# 03_Pressure_and_Flow.net
KiCad netlist of a schematic drawn in Altium Designer
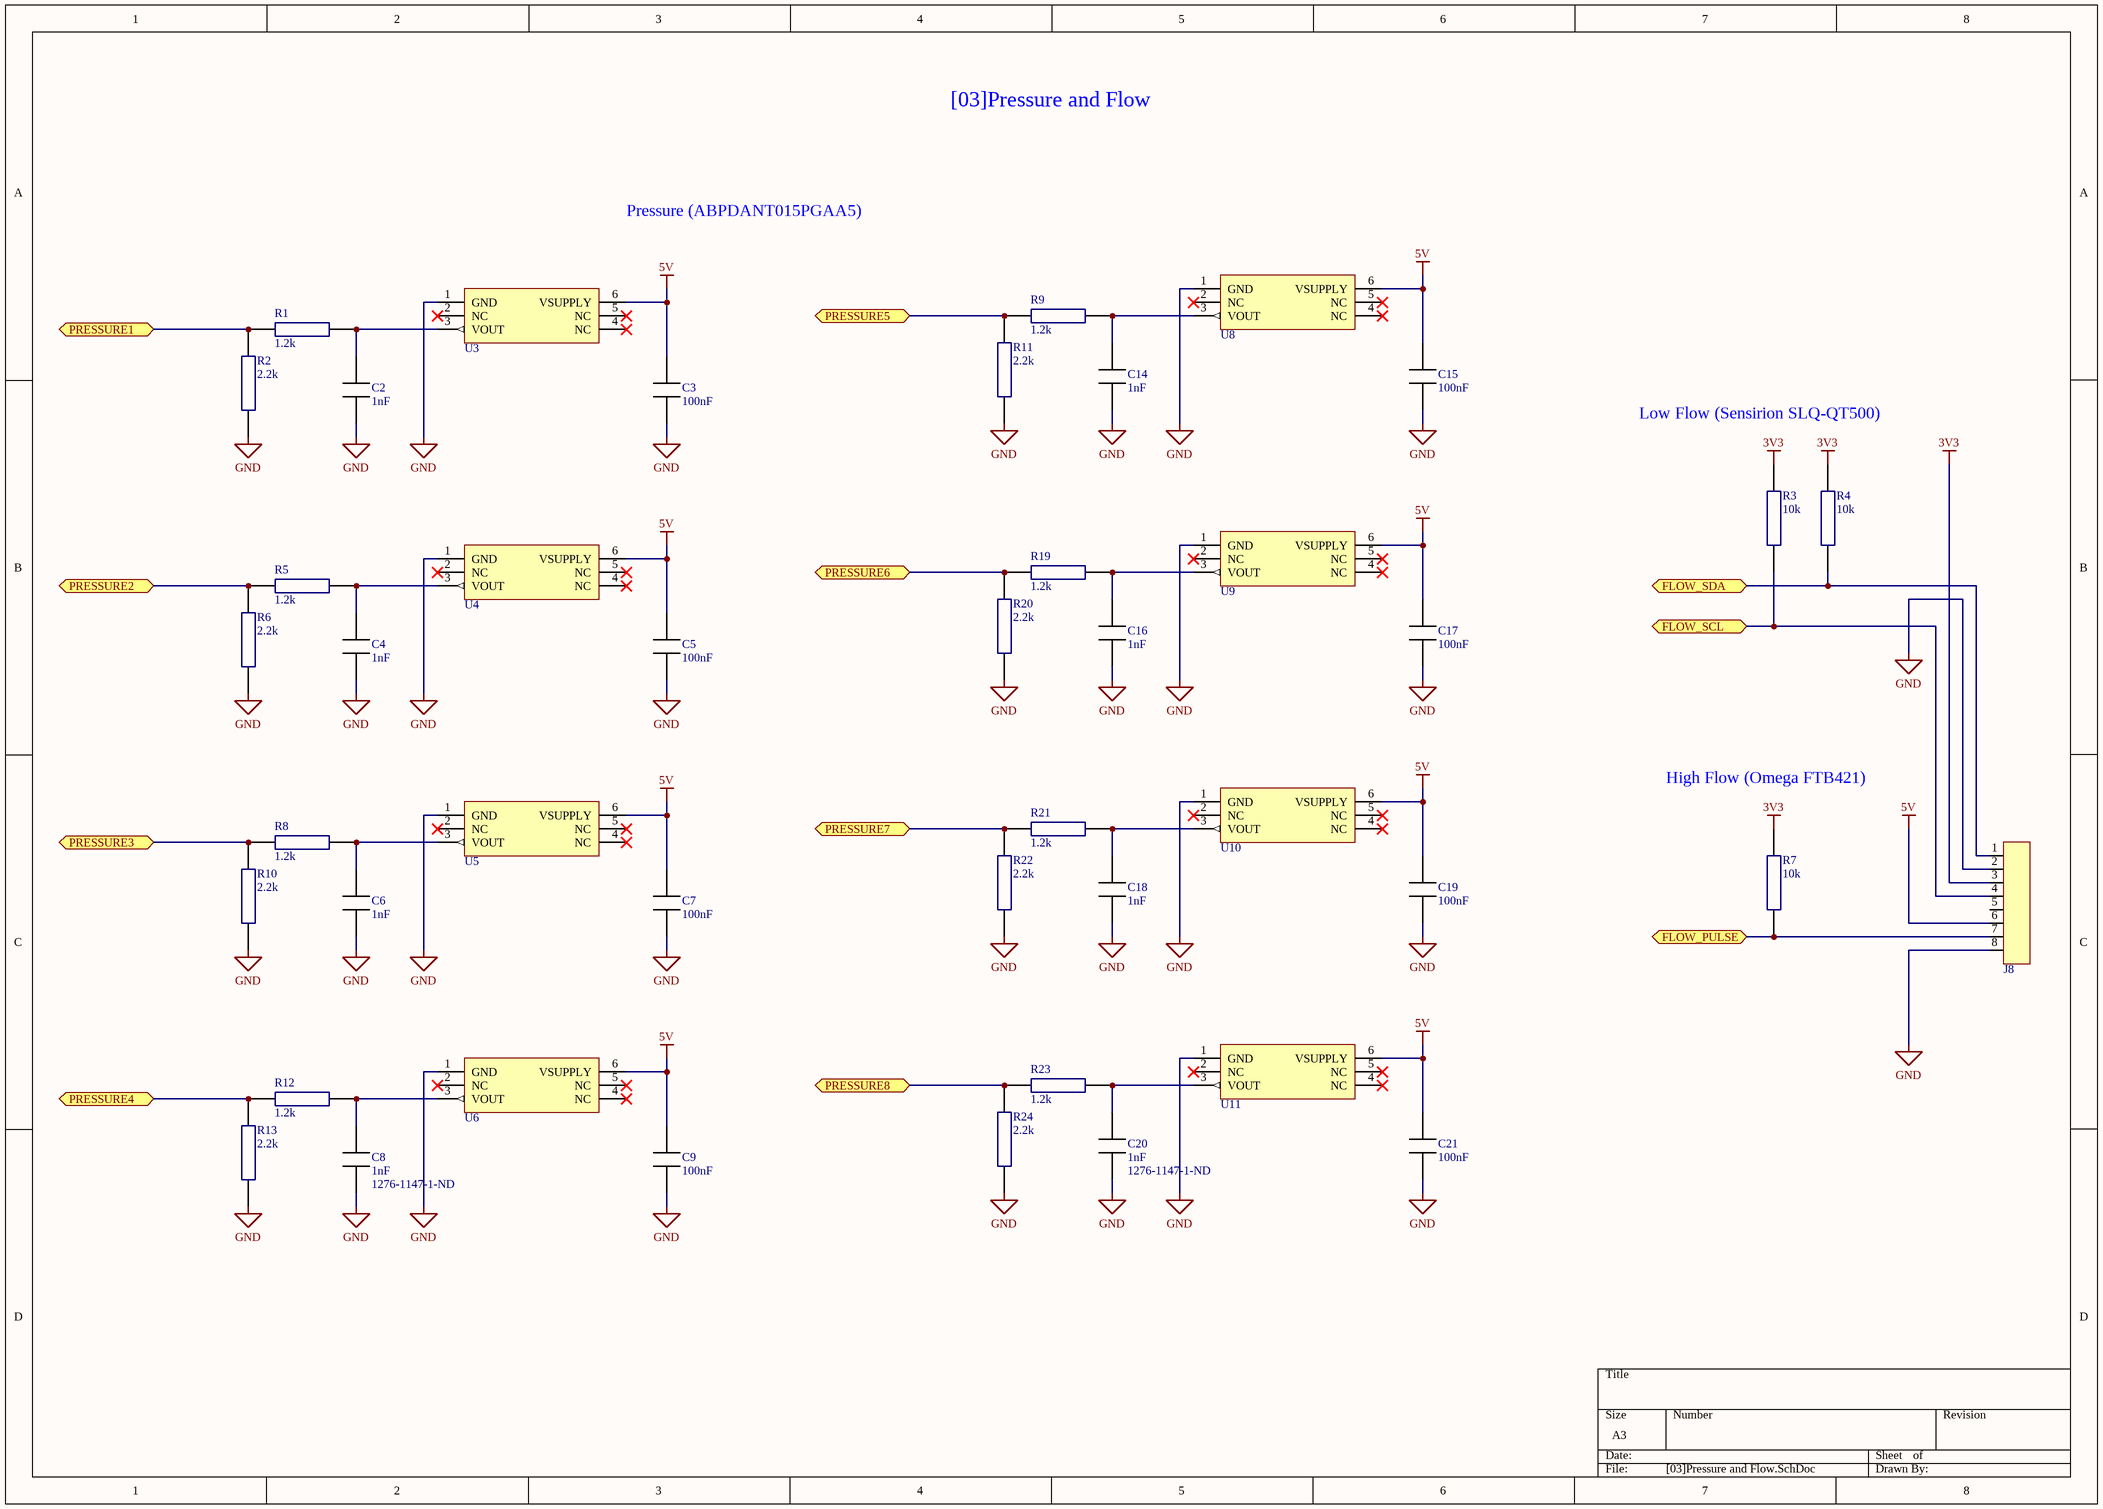
[diagram p0: [03]Pressure and Flow.SchDoc]

(export (version "E")
  (design (tool "Eeschema 10.0.6"))
  (components
    (comp (ref "C2")
      (value "1nF")
      (footprint "CAPC2012X09N")
      (description "CAP CER 1nF 50V C0G/NP0 0805")
      (fields
        (field (name "MANUFACTURER") "Samsung Electro-Mechanics America, Inc.")
        (field (name "MANUFACTURER PART NUMBER") "CL21F104ZBCNNNC")
      )
      (libsource (lib "AMMDK Parts") (part "CL21C102JBCNNNC"))
    )
    (comp (ref "C3")
      (value "100nF")
      (footprint "CAPC2012X09N")
      (description "CAP CER 0.1UF 50V Y5V 0805")
      (fields
        (field (name "MANUFACTURER") "Samsung Electro-Mechanics America, Inc.")
        (field (name "MANUFACTURER PART NUMBER") "CL21F104ZBCNNNC")
      )
      (libsource (lib "AMMDK Parts") (part "CL21F104ZBCNNNC"))
    )
    (comp (ref "C4")
      (value "1nF")
      (footprint "CAPC2012X09N")
      (description "CAP CER 1nF 50V C0G/NP0 0805")
      (fields
        (field (name "MANUFACTURER") "Samsung Electro-Mechanics America, Inc.")
        (field (name "MANUFACTURER PART NUMBER") "CL21F104ZBCNNNC")
      )
      (libsource (lib "AMMDK Parts") (part "CL21C102JBCNNNC"))
    )
    (comp (ref "C5")
      (value "100nF")
      (footprint "CAPC2012X09N")
      (description "CAP CER 0.1UF 50V Y5V 0805")
      (fields
        (field (name "MANUFACTURER") "Samsung Electro-Mechanics America, Inc.")
        (field (name "MANUFACTURER PART NUMBER") "CL21F104ZBCNNNC")
      )
      (libsource (lib "AMMDK Parts") (part "CL21F104ZBCNNNC"))
    )
    (comp (ref "C6")
      (value "1nF")
      (footprint "CAPC2012X09N")
      (description "CAP CER 1nF 50V C0G/NP0 0805")
      (fields
        (field (name "MANUFACTURER") "Samsung Electro-Mechanics America, Inc.")
        (field (name "MANUFACTURER PART NUMBER") "CL21F104ZBCNNNC")
      )
      (libsource (lib "AMMDK Parts") (part "CL21C102JBCNNNC"))
    )
    (comp (ref "C7")
      (value "100nF")
      (footprint "CAPC2012X09N")
      (description "CAP CER 0.1UF 50V Y5V 0805")
      (fields
        (field (name "MANUFACTURER") "Samsung Electro-Mechanics America, Inc.")
        (field (name "MANUFACTURER PART NUMBER") "CL21F104ZBCNNNC")
      )
      (libsource (lib "AMMDK Parts") (part "CL21F104ZBCNNNC"))
    )
    (comp (ref "C8")
      (value "1nF")
      (footprint "CAPC2012X09N")
      (description "CAP CER 1nF 50V C0G/NP0 0805")
      (fields
        (field (name "MANUFACTURER") "Samsung Electro-Mechanics America, Inc.")
        (field (name "MANUFACTURER PART NUMBER") "CL21F104ZBCNNNC")
        (field (name "SUPPLIER PART NUMBER 1") "1276-1147-1-ND")
      )
      (libsource (lib "AMMDK Parts") (part "CL21C102JBCNNNC"))
    )
    (comp (ref "C9")
      (value "100nF")
      (footprint "CAPC2012X09N")
      (description "CAP CER 0.1UF 50V Y5V 0805")
      (fields
        (field (name "MANUFACTURER") "Samsung Electro-Mechanics America, Inc.")
        (field (name "MANUFACTURER PART NUMBER") "CL21F104ZBCNNNC")
      )
      (libsource (lib "AMMDK Parts") (part "CL21F104ZBCNNNC"))
    )
    (comp (ref "C14")
      (value "1nF")
      (footprint "CAPC2012X09N")
      (description "CAP CER 1nF 50V C0G/NP0 0805")
      (fields
        (field (name "MANUFACTURER") "Samsung Electro-Mechanics America, Inc.")
        (field (name "MANUFACTURER PART NUMBER") "CL21F104ZBCNNNC")
      )
      (libsource (lib "AMMDK Parts") (part "CL21C102JBCNNNC"))
    )
    (comp (ref "C15")
      (value "100nF")
      (footprint "CAPC2012X09N")
      (description "CAP CER 0.1UF 50V Y5V 0805")
      (fields
        (field (name "MANUFACTURER") "Samsung Electro-Mechanics America, Inc.")
        (field (name "MANUFACTURER PART NUMBER") "CL21F104ZBCNNNC")
      )
      (libsource (lib "AMMDK Parts") (part "CL21F104ZBCNNNC"))
    )
    (comp (ref "C16")
      (value "1nF")
      (footprint "CAPC2012X09N")
      (description "CAP CER 1nF 50V C0G/NP0 0805")
      (fields
        (field (name "MANUFACTURER") "Samsung Electro-Mechanics America, Inc.")
        (field (name "MANUFACTURER PART NUMBER") "CL21F104ZBCNNNC")
      )
      (libsource (lib "AMMDK Parts") (part "CL21C102JBCNNNC"))
    )
    (comp (ref "C17")
      (value "100nF")
      (footprint "CAPC2012X09N")
      (description "CAP CER 0.1UF 50V Y5V 0805")
      (fields
        (field (name "MANUFACTURER") "Samsung Electro-Mechanics America, Inc.")
        (field (name "MANUFACTURER PART NUMBER") "CL21F104ZBCNNNC")
      )
      (libsource (lib "AMMDK Parts") (part "CL21F104ZBCNNNC"))
    )
    (comp (ref "C18")
      (value "1nF")
      (footprint "CAPC2012X09N")
      (description "CAP CER 1nF 50V C0G/NP0 0805")
      (fields
        (field (name "MANUFACTURER") "Samsung Electro-Mechanics America, Inc.")
        (field (name "MANUFACTURER PART NUMBER") "CL21F104ZBCNNNC")
      )
      (libsource (lib "AMMDK Parts") (part "CL21C102JBCNNNC"))
    )
    (comp (ref "C19")
      (value "100nF")
      (footprint "CAPC2012X09N")
      (description "CAP CER 0.1UF 50V Y5V 0805")
      (fields
        (field (name "MANUFACTURER") "Samsung Electro-Mechanics America, Inc.")
        (field (name "MANUFACTURER PART NUMBER") "CL21F104ZBCNNNC")
      )
      (libsource (lib "AMMDK Parts") (part "CL21F104ZBCNNNC"))
    )
    (comp (ref "C20")
      (value "1nF")
      (footprint "CAPC2012X09N")
      (description "CAP CER 1nF 50V C0G/NP0 0805")
      (fields
        (field (name "MANUFACTURER") "Samsung Electro-Mechanics America, Inc.")
        (field (name "MANUFACTURER PART NUMBER") "CL21F104ZBCNNNC")
        (field (name "SUPPLIER PART NUMBER 1") "1276-1147-1-ND")
      )
      (libsource (lib "AMMDK Parts") (part "CL21C102JBCNNNC"))
    )
    (comp (ref "C21")
      (value "100nF")
      (footprint "CAPC2012X09N")
      (description "CAP CER 0.1UF 50V Y5V 0805")
      (fields
        (field (name "MANUFACTURER") "Samsung Electro-Mechanics America, Inc.")
        (field (name "MANUFACTURER PART NUMBER") "CL21F104ZBCNNNC")
      )
      (libsource (lib "AMMDK Parts") (part "CL21F104ZBCNNNC"))
    )
    (comp (ref "J8")
      (value "1771156")
      (footprint "1771156")
      (description "CONN TERM BLK 8POS 2.5MM SMD")
      (fields (field (name "MANUFACTURER") "Phoenix Contact"))
      (libsource (lib "AMMDK Parts") (part "1771156"))
    )
    (comp (ref "R1")
      (value "1.2k")
      (footprint "RESC2012X07N_SAMSUNG")
      (description "RES SMD 1.2K OHM 1% 1/8W 0805")
      (fields
        (field (name "MANUFACTURER") "Samsung Electro-Mechanics America, Inc.")
        (field (name "MANUFACTURER PART NUMBER") "RC2012F103CS")
      )
      (libsource (lib "AMMDK Parts") (part "RC2012F122CS"))
    )
    (comp (ref "R2")
      (value "2.2k")
      (footprint "RESC2012X07N_SAMSUNG")
      (description "RES SMD 2.2K OHM 1% 1/8W 0805")
      (fields
        (field (name "MANUFACTURER") "Samsung Electro-Mechanics America, Inc.")
        (field (name "MANUFACTURER PART NUMBER") "RC2012F103CS")
      )
      (libsource (lib "AMMDK Parts") (part "RC2012F222CS"))
    )
    (comp (ref "R3")
      (value "10k")
      (footprint "RESC2012X07N_SAMSUNG")
      (description "RES SMD 10K OHM 1% 1/8W 0805")
      (fields
        (field (name "MANUFACTURER") "Samsung Electro-Mechanics America, Inc.")
        (field (name "MANUFACTURER PART NUMBER") "RC2012F103CS")
      )
      (libsource (lib "AMMDK Parts") (part "RC2012F103CS"))
    )
    (comp (ref "R4")
      (value "10k")
      (footprint "RESC2012X07N_SAMSUNG")
      (description "RES SMD 10K OHM 1% 1/8W 0805")
      (fields
        (field (name "MANUFACTURER") "Samsung Electro-Mechanics America, Inc.")
        (field (name "MANUFACTURER PART NUMBER") "RC2012F103CS")
      )
      (libsource (lib "AMMDK Parts") (part "RC2012F103CS"))
    )
    (comp (ref "R5")
      (value "1.2k")
      (footprint "RESC2012X07N_SAMSUNG")
      (description "RES SMD 1.2K OHM 1% 1/8W 0805")
      (fields
        (field (name "MANUFACTURER") "Samsung Electro-Mechanics America, Inc.")
        (field (name "MANUFACTURER PART NUMBER") "RC2012F103CS")
      )
      (libsource (lib "AMMDK Parts") (part "RC2012F122CS"))
    )
    (comp (ref "R6")
      (value "2.2k")
      (footprint "RESC2012X07N_SAMSUNG")
      (description "RES SMD 2.2K OHM 1% 1/8W 0805")
      (fields
        (field (name "MANUFACTURER") "Samsung Electro-Mechanics America, Inc.")
        (field (name "MANUFACTURER PART NUMBER") "RC2012F103CS")
      )
      (libsource (lib "AMMDK Parts") (part "RC2012F222CS"))
    )
    (comp (ref "R7")
      (value "10k")
      (footprint "RESC2012X07N_SAMSUNG")
      (description "RES SMD 10K OHM 1% 1/8W 0805")
      (fields
        (field (name "MANUFACTURER") "Samsung Electro-Mechanics America, Inc.")
        (field (name "MANUFACTURER PART NUMBER") "RC2012F103CS")
      )
      (libsource (lib "AMMDK Parts") (part "RC2012F103CS"))
    )
    (comp (ref "R8")
      (value "1.2k")
      (footprint "RESC2012X07N_SAMSUNG")
      (description "RES SMD 1.2K OHM 1% 1/8W 0805")
      (fields
        (field (name "MANUFACTURER") "Samsung Electro-Mechanics America, Inc.")
        (field (name "MANUFACTURER PART NUMBER") "RC2012F103CS")
      )
      (libsource (lib "AMMDK Parts") (part "RC2012F122CS"))
    )
    (comp (ref "R9")
      (value "1.2k")
      (footprint "RESC2012X07N_SAMSUNG")
      (description "RES SMD 1.2K OHM 1% 1/8W 0805")
      (fields
        (field (name "MANUFACTURER") "Samsung Electro-Mechanics America, Inc.")
        (field (name "MANUFACTURER PART NUMBER") "RC2012F103CS")
      )
      (libsource (lib "AMMDK Parts") (part "RC2012F122CS"))
    )
    (comp (ref "R10")
      (value "2.2k")
      (footprint "RESC2012X07N_SAMSUNG")
      (description "RES SMD 2.2K OHM 1% 1/8W 0805")
      (fields
        (field (name "MANUFACTURER") "Samsung Electro-Mechanics America, Inc.")
        (field (name "MANUFACTURER PART NUMBER") "RC2012F103CS")
      )
      (libsource (lib "AMMDK Parts") (part "RC2012F222CS"))
    )
    (comp (ref "R11")
      (value "2.2k")
      (footprint "RESC2012X07N_SAMSUNG")
      (description "RES SMD 2.2K OHM 1% 1/8W 0805")
      (fields
        (field (name "MANUFACTURER") "Samsung Electro-Mechanics America, Inc.")
        (field (name "MANUFACTURER PART NUMBER") "RC2012F103CS")
      )
      (libsource (lib "AMMDK Parts") (part "RC2012F222CS"))
    )
    (comp (ref "R12")
      (value "1.2k")
      (footprint "RESC2012X07N_SAMSUNG")
      (description "RES SMD 1.2K OHM 1% 1/8W 0805")
      (fields
        (field (name "MANUFACTURER") "Samsung Electro-Mechanics America, Inc.")
        (field (name "MANUFACTURER PART NUMBER") "RC2012F103CS")
      )
      (libsource (lib "AMMDK Parts") (part "RC2012F122CS"))
    )
    (comp (ref "R13")
      (value "2.2k")
      (footprint "RESC2012X07N_SAMSUNG")
      (description "RES SMD 2.2K OHM 1% 1/8W 0805")
      (fields
        (field (name "MANUFACTURER") "Samsung Electro-Mechanics America, Inc.")
        (field (name "MANUFACTURER PART NUMBER") "RC2012F103CS")
      )
      (libsource (lib "AMMDK Parts") (part "RC2012F222CS"))
    )
    (comp (ref "R19")
      (value "1.2k")
      (footprint "RESC2012X07N_SAMSUNG")
      (description "RES SMD 1.2K OHM 1% 1/8W 0805")
      (fields
        (field (name "MANUFACTURER") "Samsung Electro-Mechanics America, Inc.")
        (field (name "MANUFACTURER PART NUMBER") "RC2012F103CS")
      )
      (libsource (lib "AMMDK Parts") (part "RC2012F122CS"))
    )
    (comp (ref "R20")
      (value "2.2k")
      (footprint "RESC2012X07N_SAMSUNG")
      (description "RES SMD 2.2K OHM 1% 1/8W 0805")
      (fields
        (field (name "MANUFACTURER") "Samsung Electro-Mechanics America, Inc.")
        (field (name "MANUFACTURER PART NUMBER") "RC2012F103CS")
      )
      (libsource (lib "AMMDK Parts") (part "RC2012F222CS"))
    )
    (comp (ref "R21")
      (value "1.2k")
      (footprint "RESC2012X07N_SAMSUNG")
      (description "RES SMD 1.2K OHM 1% 1/8W 0805")
      (fields
        (field (name "MANUFACTURER") "Samsung Electro-Mechanics America, Inc.")
        (field (name "MANUFACTURER PART NUMBER") "RC2012F103CS")
      )
      (libsource (lib "AMMDK Parts") (part "RC2012F122CS"))
    )
    (comp (ref "R22")
      (value "2.2k")
      (footprint "RESC2012X07N_SAMSUNG")
      (description "RES SMD 2.2K OHM 1% 1/8W 0805")
      (fields
        (field (name "MANUFACTURER") "Samsung Electro-Mechanics America, Inc.")
        (field (name "MANUFACTURER PART NUMBER") "RC2012F103CS")
      )
      (libsource (lib "AMMDK Parts") (part "RC2012F222CS"))
    )
    (comp (ref "R23")
      (value "1.2k")
      (footprint "RESC2012X07N_SAMSUNG")
      (description "RES SMD 1.2K OHM 1% 1/8W 0805")
      (fields
        (field (name "MANUFACTURER") "Samsung Electro-Mechanics America, Inc.")
        (field (name "MANUFACTURER PART NUMBER") "RC2012F103CS")
      )
      (libsource (lib "AMMDK Parts") (part "RC2012F122CS"))
    )
    (comp (ref "R24")
      (value "2.2k")
      (footprint "RESC2012X07N_SAMSUNG")
      (description "RES SMD 2.2K OHM 1% 1/8W 0805")
      (fields
        (field (name "MANUFACTURER") "Samsung Electro-Mechanics America, Inc.")
        (field (name "MANUFACTURER PART NUMBER") "RC2012F103CS")
      )
      (libsource (lib "AMMDK Parts") (part "RC2012F222CS"))
    )
    (comp (ref "U3")
      (value "ABPDANT015PGAA5_SMD")
      (footprint "DIP6 SMD")
      (description "Pressure Sensor 15 PSIG")
      (libsource (lib "AMMDK Parts") (part "ABPDANT015PGAA5_SMD"))
    )
    (comp (ref "U4")
      (value "ABPDANT015PGAA5_SMD")
      (footprint "DIP6 SMD")
      (description "Pressure Sensor 15 PSIG")
      (libsource (lib "AMMDK Parts") (part "ABPDANT015PGAA5_SMD"))
    )
    (comp (ref "U5")
      (value "ABPDANT015PGAA5_SMD")
      (footprint "DIP6 SMD")
      (description "Pressure Sensor 15 PSIG")
      (libsource (lib "AMMDK Parts") (part "ABPDANT015PGAA5_SMD"))
    )
    (comp (ref "U6")
      (value "ABPDANT015PGAA5_SMD")
      (footprint "DIP6 SMD")
      (description "Pressure Sensor 15 PSIG")
      (libsource (lib "AMMDK Parts") (part "ABPDANT015PGAA5_SMD"))
    )
    (comp (ref "U8")
      (value "ABPDANT015PGAA5_SMD")
      (footprint "DIP6 SMD")
      (description "Pressure Sensor 15 PSIG")
      (libsource (lib "AMMDK Parts") (part "ABPDANT015PGAA5_SMD"))
    )
    (comp (ref "U9")
      (value "ABPDANT015PGAA5_SMD")
      (footprint "DIP6 SMD")
      (description "Pressure Sensor 15 PSIG")
      (libsource (lib "AMMDK Parts") (part "ABPDANT015PGAA5_SMD"))
    )
    (comp (ref "U10")
      (value "ABPDANT015PGAA5_SMD")
      (footprint "DIP6 SMD")
      (description "Pressure Sensor 15 PSIG")
      (libsource (lib "AMMDK Parts") (part "ABPDANT015PGAA5_SMD"))
    )
    (comp (ref "U11")
      (value "ABPDANT015PGAA5_SMD")
      (footprint "DIP6 SMD")
      (description "Pressure Sensor 15 PSIG")
      (libsource (lib "AMMDK Parts") (part "ABPDANT015PGAA5_SMD"))
    )
  )
  (nets
    (net (code "1") (name "/FLOW_PULSE") (class "Default")
      (node (ref "J8") (pin "7") (pinfunction "7_7") (pintype "passive"))
      (node (ref "R7") (pin "1") (pinfunction "1_1") (pintype "passive"))
    )
    (net (code "2") (name "/FLOW_SCL") (class "Default")
      (node (ref "J8") (pin "4") (pinfunction "4_4") (pintype "passive"))
      (node (ref "R3") (pin "1") (pinfunction "1_1") (pintype "passive"))
    )
    (net (code "3") (name "/FLOW_SDA") (class "Default")
      (node (ref "J8") (pin "1") (pinfunction "1_1") (pintype "passive"))
      (node (ref "R4") (pin "1") (pinfunction "1_1") (pintype "passive"))
    )
    (net (code "4") (name "/PRESSURE1") (class "Default")
      (node (ref "R1") (pin "1") (pinfunction "1_1") (pintype "passive"))
      (node (ref "R2") (pin "2") (pinfunction "2_2") (pintype "passive"))
    )
    (net (code "5") (name "/PRESSURE2") (class "Default")
      (node (ref "R5") (pin "1") (pinfunction "1_1") (pintype "passive"))
      (node (ref "R6") (pin "2") (pinfunction "2_2") (pintype "passive"))
    )
    (net (code "6") (name "/PRESSURE3") (class "Default")
      (node (ref "R10") (pin "2") (pinfunction "2_2") (pintype "passive"))
      (node (ref "R8") (pin "1") (pinfunction "1_1") (pintype "passive"))
    )
    (net (code "7") (name "/PRESSURE4") (class "Default")
      (node (ref "R12") (pin "1") (pinfunction "1_1") (pintype "passive"))
      (node (ref "R13") (pin "2") (pinfunction "2_2") (pintype "passive"))
    )
    (net (code "8") (name "/PRESSURE5") (class "Default")
      (node (ref "R11") (pin "2") (pinfunction "2_2") (pintype "passive"))
      (node (ref "R9") (pin "1") (pinfunction "1_1") (pintype "passive"))
    )
    (net (code "9") (name "/PRESSURE6") (class "Default")
      (node (ref "R19") (pin "1") (pinfunction "1_1") (pintype "passive"))
      (node (ref "R20") (pin "2") (pinfunction "2_2") (pintype "passive"))
    )
    (net (code "10") (name "/PRESSURE7") (class "Default")
      (node (ref "R21") (pin "1") (pinfunction "1_1") (pintype "passive"))
      (node (ref "R22") (pin "2") (pinfunction "2_2") (pintype "passive"))
    )
    (net (code "11") (name "/PRESSURE8") (class "Default")
      (node (ref "R23") (pin "1") (pinfunction "1_1") (pintype "passive"))
      (node (ref "R24") (pin "2") (pinfunction "2_2") (pintype "passive"))
    )
    (net (code "12") (name "3V3") (class "Default")
      (node (ref "J8") (pin "3") (pinfunction "3_3") (pintype "passive"))
      (node (ref "R3") (pin "2") (pinfunction "2_2") (pintype "passive"))
      (node (ref "R4") (pin "2") (pinfunction "2_2") (pintype "passive"))
      (node (ref "R7") (pin "2") (pinfunction "2_2") (pintype "passive"))
    )
    (net (code "13") (name "5V") (class "Default")
      (node (ref "C15") (pin "2") (pinfunction "2_2") (pintype "passive"))
      (node (ref "C17") (pin "2") (pinfunction "2_2") (pintype "passive"))
      (node (ref "C19") (pin "2") (pinfunction "2_2") (pintype "passive"))
      (node (ref "C21") (pin "2") (pinfunction "2_2") (pintype "passive"))
      (node (ref "C3") (pin "2") (pinfunction "2_2") (pintype "passive"))
      (node (ref "C5") (pin "2") (pinfunction "2_2") (pintype "passive"))
      (node (ref "C7") (pin "2") (pinfunction "2_2") (pintype "passive"))
      (node (ref "C9") (pin "2") (pinfunction "2_2") (pintype "passive"))
      (node (ref "J8") (pin "6") (pinfunction "6_6") (pintype "passive"))
      (node (ref "U10") (pin "6") (pinfunction "VSUPPLY_6") (pintype "power_in"))
      (node (ref "U11") (pin "6") (pinfunction "VSUPPLY_6") (pintype "power_in"))
      (node (ref "U3") (pin "6") (pinfunction "VSUPPLY_6") (pintype "power_in"))
      (node (ref "U4") (pin "6") (pinfunction "VSUPPLY_6") (pintype "power_in"))
      (node (ref "U5") (pin "6") (pinfunction "VSUPPLY_6") (pintype "power_in"))
      (node (ref "U6") (pin "6") (pinfunction "VSUPPLY_6") (pintype "power_in"))
      (node (ref "U8") (pin "6") (pinfunction "VSUPPLY_6") (pintype "power_in"))
      (node (ref "U9") (pin "6") (pinfunction "VSUPPLY_6") (pintype "power_in"))
    )
    (net (code "14") (name "GND") (class "Default")
      (node (ref "C14") (pin "1") (pinfunction "1_1") (pintype "passive"))
      (node (ref "C15") (pin "1") (pinfunction "1_1") (pintype "passive"))
      (node (ref "C16") (pin "1") (pinfunction "1_1") (pintype "passive"))
      (node (ref "C17") (pin "1") (pinfunction "1_1") (pintype "passive"))
      (node (ref "C18") (pin "1") (pinfunction "1_1") (pintype "passive"))
      (node (ref "C19") (pin "1") (pinfunction "1_1") (pintype "passive"))
      (node (ref "C2") (pin "1") (pinfunction "1_1") (pintype "passive"))
      (node (ref "C20") (pin "1") (pinfunction "1_1") (pintype "passive"))
      (node (ref "C21") (pin "1") (pinfunction "1_1") (pintype "passive"))
      (node (ref "C3") (pin "1") (pinfunction "1_1") (pintype "passive"))
      (node (ref "C4") (pin "1") (pinfunction "1_1") (pintype "passive"))
      (node (ref "C5") (pin "1") (pinfunction "1_1") (pintype "passive"))
      (node (ref "C6") (pin "1") (pinfunction "1_1") (pintype "passive"))
      (node (ref "C7") (pin "1") (pinfunction "1_1") (pintype "passive"))
      (node (ref "C8") (pin "1") (pinfunction "1_1") (pintype "passive"))
      (node (ref "C9") (pin "1") (pinfunction "1_1") (pintype "passive"))
      (node (ref "J8") (pin "2") (pinfunction "2_2") (pintype "passive"))
      (node (ref "J8") (pin "8") (pinfunction "8_8") (pintype "passive"))
      (node (ref "R10") (pin "1") (pinfunction "1_1") (pintype "passive"))
      (node (ref "R11") (pin "1") (pinfunction "1_1") (pintype "passive"))
      (node (ref "R13") (pin "1") (pinfunction "1_1") (pintype "passive"))
      (node (ref "R2") (pin "1") (pinfunction "1_1") (pintype "passive"))
      (node (ref "R20") (pin "1") (pinfunction "1_1") (pintype "passive"))
      (node (ref "R22") (pin "1") (pinfunction "1_1") (pintype "passive"))
      (node (ref "R24") (pin "1") (pinfunction "1_1") (pintype "passive"))
      (node (ref "R6") (pin "1") (pinfunction "1_1") (pintype "passive"))
      (node (ref "U10") (pin "1") (pinfunction "GND_1") (pintype "power_in"))
      (node (ref "U11") (pin "1") (pinfunction "GND_1") (pintype "power_in"))
      (node (ref "U3") (pin "1") (pinfunction "GND_1") (pintype "power_in"))
      (node (ref "U4") (pin "1") (pinfunction "GND_1") (pintype "power_in"))
      (node (ref "U5") (pin "1") (pinfunction "GND_1") (pintype "power_in"))
      (node (ref "U6") (pin "1") (pinfunction "GND_1") (pintype "power_in"))
      (node (ref "U8") (pin "1") (pinfunction "GND_1") (pintype "power_in"))
      (node (ref "U9") (pin "1") (pinfunction "GND_1") (pintype "power_in"))
    )
    (net (code "15") (name "Net-(U3-VOUT)") (class "Default")
      (node (ref "C2") (pin "2") (pinfunction "2_2") (pintype "passive"))
      (node (ref "R1") (pin "2") (pinfunction "2_2") (pintype "passive"))
      (node (ref "U3") (pin "3") (pinfunction "VOUT_3") (pintype "output"))
    )
    (net (code "16") (name "Net-(U4-VOUT)") (class "Default")
      (node (ref "C4") (pin "2") (pinfunction "2_2") (pintype "passive"))
      (node (ref "R5") (pin "2") (pinfunction "2_2") (pintype "passive"))
      (node (ref "U4") (pin "3") (pinfunction "VOUT_3") (pintype "output"))
    )
    (net (code "17") (name "Net-(U5-VOUT)") (class "Default")
      (node (ref "C6") (pin "2") (pinfunction "2_2") (pintype "passive"))
      (node (ref "R8") (pin "2") (pinfunction "2_2") (pintype "passive"))
      (node (ref "U5") (pin "3") (pinfunction "VOUT_3") (pintype "output"))
    )
    (net (code "18") (name "Net-(U6-VOUT)") (class "Default")
      (node (ref "C8") (pin "2") (pinfunction "2_2") (pintype "passive"))
      (node (ref "R12") (pin "2") (pinfunction "2_2") (pintype "passive"))
      (node (ref "U6") (pin "3") (pinfunction "VOUT_3") (pintype "output"))
    )
    (net (code "19") (name "Net-(U8-VOUT)") (class "Default")
      (node (ref "C14") (pin "2") (pinfunction "2_2") (pintype "passive"))
      (node (ref "R9") (pin "2") (pinfunction "2_2") (pintype "passive"))
      (node (ref "U8") (pin "3") (pinfunction "VOUT_3") (pintype "output"))
    )
    (net (code "20") (name "Net-(U9-VOUT)") (class "Default")
      (node (ref "C16") (pin "2") (pinfunction "2_2") (pintype "passive"))
      (node (ref "R19") (pin "2") (pinfunction "2_2") (pintype "passive"))
      (node (ref "U9") (pin "3") (pinfunction "VOUT_3") (pintype "output"))
    )
    (net (code "21") (name "Net-(U10-VOUT)") (class "Default")
      (node (ref "C18") (pin "2") (pinfunction "2_2") (pintype "passive"))
      (node (ref "R21") (pin "2") (pinfunction "2_2") (pintype "passive"))
      (node (ref "U10") (pin "3") (pinfunction "VOUT_3") (pintype "output"))
    )
    (net (code "22") (name "Net-(U11-VOUT)") (class "Default")
      (node (ref "C20") (pin "2") (pinfunction "2_2") (pintype "passive"))
      (node (ref "R23") (pin "2") (pinfunction "2_2") (pintype "passive"))
      (node (ref "U11") (pin "3") (pinfunction "VOUT_3") (pintype "output"))
    )
    (net (code "23") (name "unconnected-(J8-Pad5)") (class "Default")
      (node (ref "J8") (pin "5") (pinfunction "5_5") (pintype "passive"))
    )
    (net (code "24") (name "unconnected-(U3-NC-Pad2)") (class "Default")
      (node (ref "U3") (pin "2") (pinfunction "NC_2") (pintype "passive+no_connect"))
    )
    (net (code "25") (name "unconnected-(U3-NC-Pad4)") (class "Default")
      (node (ref "U3") (pin "4") (pinfunction "NC_4") (pintype "passive+no_connect"))
    )
    (net (code "26") (name "unconnected-(U3-NC-Pad5)") (class "Default")
      (node (ref "U3") (pin "5") (pinfunction "NC_5") (pintype "passive+no_connect"))
    )
    (net (code "27") (name "unconnected-(U4-NC-Pad2)") (class "Default")
      (node (ref "U4") (pin "2") (pinfunction "NC_2") (pintype "passive+no_connect"))
    )
    (net (code "28") (name "unconnected-(U4-NC-Pad4)") (class "Default")
      (node (ref "U4") (pin "4") (pinfunction "NC_4") (pintype "passive+no_connect"))
    )
    (net (code "29") (name "unconnected-(U4-NC-Pad5)") (class "Default")
      (node (ref "U4") (pin "5") (pinfunction "NC_5") (pintype "passive+no_connect"))
    )
    (net (code "30") (name "unconnected-(U5-NC-Pad2)") (class "Default")
      (node (ref "U5") (pin "2") (pinfunction "NC_2") (pintype "passive+no_connect"))
    )
    (net (code "31") (name "unconnected-(U5-NC-Pad4)") (class "Default")
      (node (ref "U5") (pin "4") (pinfunction "NC_4") (pintype "passive+no_connect"))
    )
    (net (code "32") (name "unconnected-(U5-NC-Pad5)") (class "Default")
      (node (ref "U5") (pin "5") (pinfunction "NC_5") (pintype "passive+no_connect"))
    )
    (net (code "33") (name "unconnected-(U6-NC-Pad2)") (class "Default")
      (node (ref "U6") (pin "2") (pinfunction "NC_2") (pintype "passive+no_connect"))
    )
    (net (code "34") (name "unconnected-(U6-NC-Pad4)") (class "Default")
      (node (ref "U6") (pin "4") (pinfunction "NC_4") (pintype "passive+no_connect"))
    )
    (net (code "35") (name "unconnected-(U6-NC-Pad5)") (class "Default")
      (node (ref "U6") (pin "5") (pinfunction "NC_5") (pintype "passive+no_connect"))
    )
    (net (code "36") (name "unconnected-(U8-NC-Pad2)") (class "Default")
      (node (ref "U8") (pin "2") (pinfunction "NC_2") (pintype "passive+no_connect"))
    )
    (net (code "37") (name "unconnected-(U8-NC-Pad4)") (class "Default")
      (node (ref "U8") (pin "4") (pinfunction "NC_4") (pintype "passive+no_connect"))
    )
    (net (code "38") (name "unconnected-(U8-NC-Pad5)") (class "Default")
      (node (ref "U8") (pin "5") (pinfunction "NC_5") (pintype "passive+no_connect"))
    )
    (net (code "39") (name "unconnected-(U9-NC-Pad2)") (class "Default")
      (node (ref "U9") (pin "2") (pinfunction "NC_2") (pintype "passive+no_connect"))
    )
    (net (code "40") (name "unconnected-(U9-NC-Pad4)") (class "Default")
      (node (ref "U9") (pin "4") (pinfunction "NC_4") (pintype "passive+no_connect"))
    )
    (net (code "41") (name "unconnected-(U9-NC-Pad5)") (class "Default")
      (node (ref "U9") (pin "5") (pinfunction "NC_5") (pintype "passive+no_connect"))
    )
    (net (code "42") (name "unconnected-(U10-NC-Pad2)") (class "Default")
      (node (ref "U10") (pin "2") (pinfunction "NC_2") (pintype "passive+no_connect"))
    )
    (net (code "43") (name "unconnected-(U10-NC-Pad4)") (class "Default")
      (node (ref "U10") (pin "4") (pinfunction "NC_4") (pintype "passive+no_connect"))
    )
    (net (code "44") (name "unconnected-(U10-NC-Pad5)") (class "Default")
      (node (ref "U10") (pin "5") (pinfunction "NC_5") (pintype "passive+no_connect"))
    )
    (net (code "45") (name "unconnected-(U11-NC-Pad2)") (class "Default")
      (node (ref "U11") (pin "2") (pinfunction "NC_2") (pintype "passive+no_connect"))
    )
    (net (code "46") (name "unconnected-(U11-NC-Pad4)") (class "Default")
      (node (ref "U11") (pin "4") (pinfunction "NC_4") (pintype "passive+no_connect"))
    )
    (net (code "47") (name "unconnected-(U11-NC-Pad5)") (class "Default")
      (node (ref "U11") (pin "5") (pinfunction "NC_5") (pintype "passive+no_connect"))
    )
  )
)
